# Ldo_-16V5_-15V0.net
KiCad netlist of a schematic drawn in Altium Designer
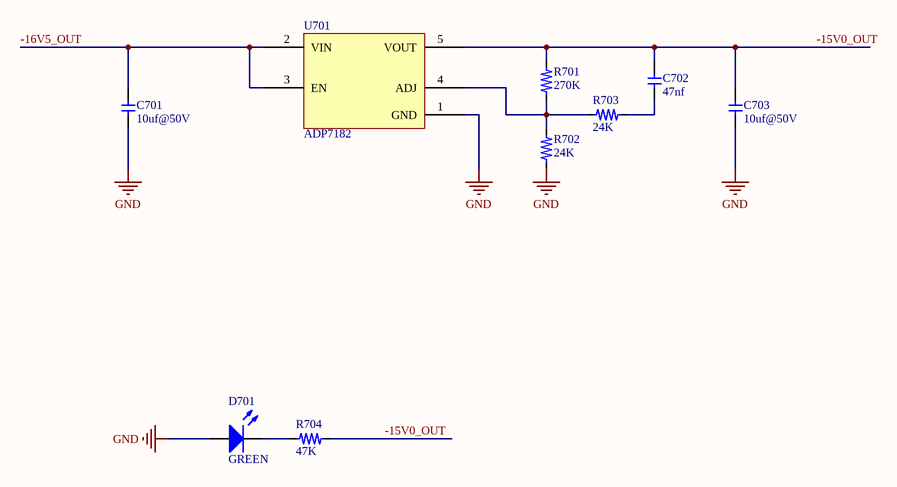
[diagram p0: Ldo.-16V5.-15V0.SchDoc]

(export (version "E")
  (design (tool "Eeschema 10.0.6"))
  (components
    (comp (ref "C701")
      (value "10uf@50V")
      (footprint "C1210")
      (fields (field (name "Comment") "Cap"))
      (libsource (lib "carrot_lib") (part "Cap"))
    )
    (comp (ref "C702")
      (value "47nf")
      (footprint "C0603")
      (fields (field (name "Comment") "Cap"))
      (libsource (lib "carrot_lib") (part "Cap"))
    )
    (comp (ref "C703")
      (value "10uf@50V")
      (footprint "C1210")
      (fields (field (name "Comment") "Cap"))
      (libsource (lib "carrot_lib") (part "Cap"))
    )
    (comp (ref "D701")
      (value "GREEN")
      (footprint "LED0603")
      (fields (field (name "Comment") "LED"))
      (libsource (lib "carrot_lib") (part "LED"))
    )
    (comp (ref "R701")
      (value "270K")
      (footprint "R0603")
      (description "电阻")
      (fields (field (name "Comment") "Res"))
      (libsource (lib "carrot_lib") (part "Res"))
    )
    (comp (ref "R702")
      (value "24K")
      (footprint "R0603")
      (description "电阻")
      (fields (field (name "Comment") "Res"))
      (libsource (lib "carrot_lib") (part "Res"))
    )
    (comp (ref "R703")
      (value "24K")
      (footprint "R0603")
      (description "电阻")
      (fields (field (name "Comment") "Res"))
      (libsource (lib "carrot_lib") (part "Res"))
    )
    (comp (ref "R704")
      (value "47K")
      (footprint "R0603")
      (description "电阻")
      (fields (field (name "Comment") "Res"))
      (libsource (lib "carrot_lib") (part "Res"))
    )
    (comp (ref "U701")
      (value "ADP7182")
      (footprint "ADP7182-TSOT5")
      (description "–28 V, −200 mA, Low Noise, Linear Regulator")
      (libsource (lib "carrot_lib") (part "ADP7182AUJ"))
    )
  )
  (nets
    (net (code "1") (name "/-15V0_OUT") (class "Default")
      (node (ref "C702") (pin "1") (pinfunction "1_1") (pintype "passive"))
      (node (ref "C703") (pin "2") (pinfunction "2_2") (pintype "passive"))
      (node (ref "R701") (pin "2") (pinfunction "2_2") (pintype "passive"))
      (node (ref "R704") (pin "1") (pinfunction "1_1") (pintype "passive"))
      (node (ref "U701") (pin "5") (pinfunction "VOUT_5") (pintype "passive"))
    )
    (net (code "2") (name "/-16V5_OUT") (class "Default")
      (node (ref "C701") (pin "2") (pinfunction "2_2") (pintype "passive"))
      (node (ref "U701") (pin "2") (pinfunction "VIN_2") (pintype "passive"))
      (node (ref "U701") (pin "3") (pinfunction "EN_3") (pintype "passive"))
    )
    (net (code "3") (name "GND") (class "Default")
      (node (ref "C701") (pin "1") (pinfunction "1_1") (pintype "passive"))
      (node (ref "C703") (pin "1") (pinfunction "1_1") (pintype "passive"))
      (node (ref "D701") (pin "1") (pinfunction "A_1") (pintype "passive"))
      (node (ref "R702") (pin "1") (pinfunction "1_1") (pintype "passive"))
      (node (ref "U701") (pin "1") (pinfunction "GND_1") (pintype "passive"))
    )
    (net (code "4") (name "Net-(C702-Pad2)") (class "Default")
      (node (ref "C702") (pin "2") (pinfunction "2_2") (pintype "passive"))
      (node (ref "R703") (pin "1") (pinfunction "1_1") (pintype "passive"))
    )
    (net (code "5") (name "Net-(D701-K)") (class "Default")
      (node (ref "D701") (pin "2") (pinfunction "K_2") (pintype "passive"))
      (node (ref "R704") (pin "2") (pinfunction "2_2") (pintype "passive"))
    )
    (net (code "6") (name "Net-(U701-ADJ)") (class "Default")
      (node (ref "R701") (pin "1") (pinfunction "1_1") (pintype "passive"))
      (node (ref "R702") (pin "2") (pinfunction "2_2") (pintype "passive"))
      (node (ref "R703") (pin "2") (pinfunction "2_2") (pintype "passive"))
      (node (ref "U701") (pin "4") (pinfunction "ADJ_4") (pintype "passive"))
    )
  )
)
